# Sheet_1.net
KiCad netlist of a schematic drawn in Altium Designer
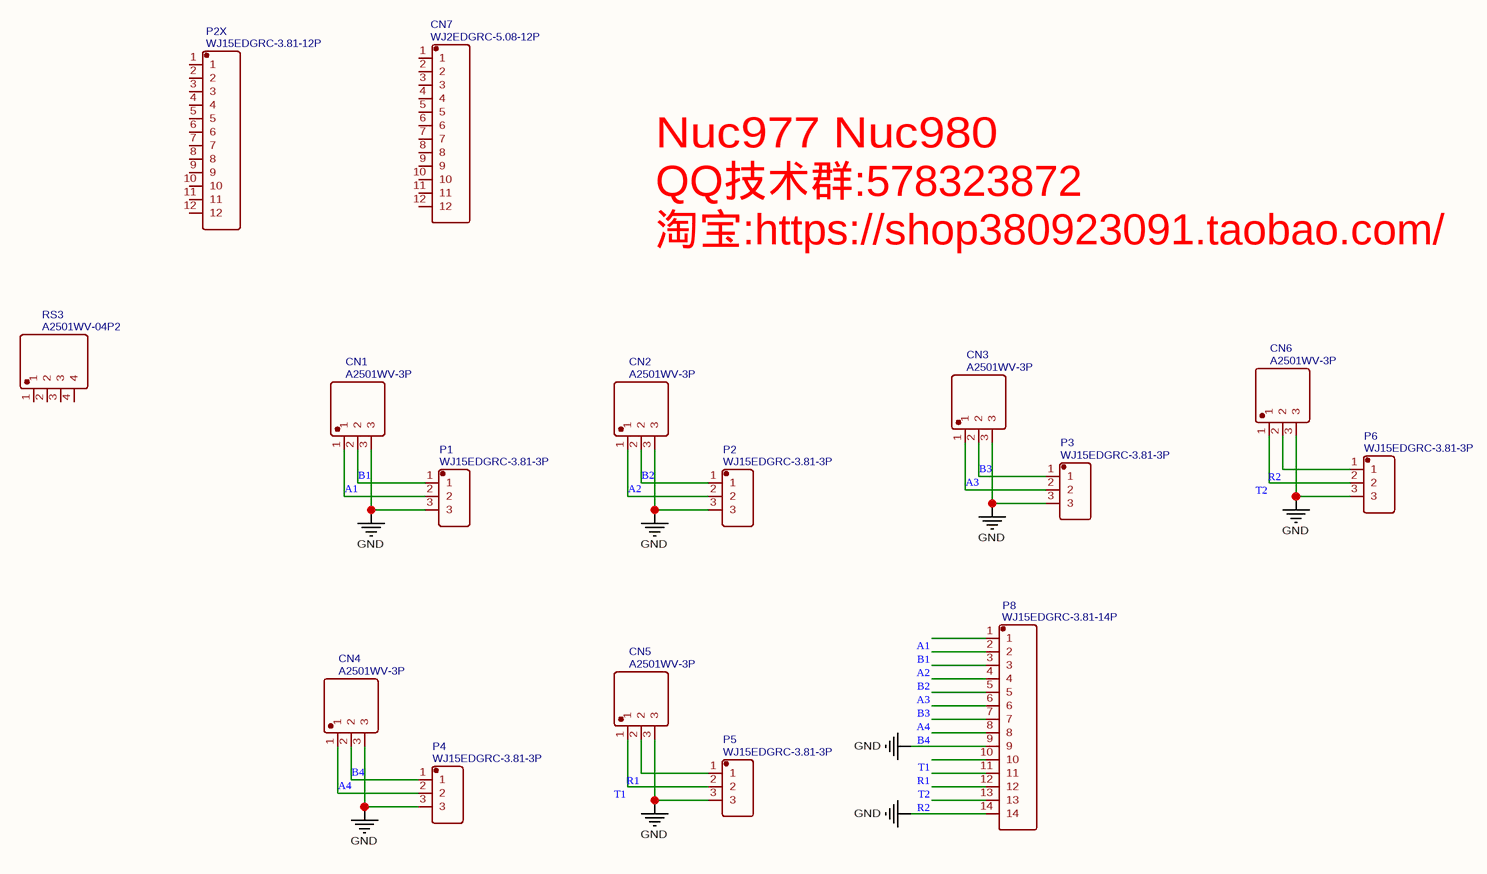
[diagram p0: Sheet_1.schdoc]

(export (version "E")
  (design (tool "Eeschema 10.0.6"))
  (components
    (comp (ref "CN1")
      (value "A2501WV-3P")
      (fields (field (name "BOM_SUPPLIER PART") "C225389") (field (name "CONTRIBUTOR") "LCSC"))
      (libsource (lib "altium-import") (part "root_1_A2501WV-3P_"))
    )
    (comp (ref "CN2")
      (value "A2501WV-3P")
      (fields (field (name "BOM_SUPPLIER PART") "C225389") (field (name "CONTRIBUTOR") "LCSC"))
      (libsource (lib "altium-import") (part "root_1_A2501WV-3P_"))
    )
    (comp (ref "CN3")
      (value "A2501WV-3P")
      (fields (field (name "BOM_SUPPLIER PART") "C225389") (field (name "CONTRIBUTOR") "LCSC"))
      (libsource (lib "altium-import") (part "root_1_A2501WV-3P_"))
    )
    (comp (ref "CN4")
      (value "A2501WV-3P")
      (fields (field (name "BOM_SUPPLIER PART") "C225389") (field (name "CONTRIBUTOR") "LCSC"))
      (libsource (lib "altium-import") (part "root_1_A2501WV-3P_"))
    )
    (comp (ref "CN5")
      (value "A2501WV-3P")
      (fields (field (name "BOM_SUPPLIER PART") "C225389") (field (name "CONTRIBUTOR") "LCSC"))
      (libsource (lib "altium-import") (part "root_1_A2501WV-3P_"))
    )
    (comp (ref "CN6")
      (value "A2501WV-3P")
      (fields (field (name "BOM_SUPPLIER PART") "C225389") (field (name "CONTRIBUTOR") "LCSC"))
      (libsource (lib "altium-import") (part "root_1_A2501WV-3P_"))
    )
    (comp (ref "CN7")
      (value "WJ2EDGRC-5.08-12P")
      (fields (field (name "BOM_SUPPLIER PART") "C127848") (field (name "CONTRIBUTOR") "LCSC"))
      (libsource (lib "altium-import") (part "root_0_WJ2EDGRC-5.08-12P_"))
    )
    (comp (ref "P1")
      (value "WJ15EDGRC-3.81-3P")
      (fields (field (name "BOM_SUPPLIER PART") "C8406"))
      (libsource (lib "altium-import") (part "root_0_WJ15EDGRC-3.81-3P_"))
    )
    (comp (ref "P2")
      (value "WJ15EDGRC-3.81-3P")
      (fields (field (name "BOM_SUPPLIER PART") "C8406"))
      (libsource (lib "altium-import") (part "root_0_WJ15EDGRC-3.81-3P_"))
    )
    (comp (ref "P2X")
      (value "WJ15EDGRC-3.81-12P")
      (fields (field (name "BOM_SUPPLIER PART") "C35591"))
      (libsource (lib "altium-import") (part "root_0_WJ15EDGRC-3.81-12P_"))
    )
    (comp (ref "P3")
      (value "WJ15EDGRC-3.81-3P")
      (fields (field (name "BOM_SUPPLIER PART") "C8406"))
      (libsource (lib "altium-import") (part "root_0_WJ15EDGRC-3.81-3P_"))
    )
    (comp (ref "P4")
      (value "WJ15EDGRC-3.81-3P")
      (fields (field (name "BOM_SUPPLIER PART") "C8406"))
      (libsource (lib "altium-import") (part "root_0_WJ15EDGRC-3.81-3P_"))
    )
    (comp (ref "P5")
      (value "WJ15EDGRC-3.81-3P")
      (fields (field (name "BOM_SUPPLIER PART") "C8406"))
      (libsource (lib "altium-import") (part "root_0_WJ15EDGRC-3.81-3P_"))
    )
    (comp (ref "P6")
      (value "WJ15EDGRC-3.81-3P")
      (fields (field (name "BOM_SUPPLIER PART") "C8406"))
      (libsource (lib "altium-import") (part "root_0_WJ15EDGRC-3.81-3P_"))
    )
    (comp (ref "P8")
      (value "WJ15EDGRC-3.81-14P")
      (fields (field (name "BOM_SUPPLIER PART") "C31933"))
      (libsource (lib "altium-import") (part "root_0_WJ15EDGRC-3.81-14P_"))
    )
    (comp (ref "RS3")
      (value "A2501WV-04P2")
      (fields (field (name "BOM_SUPPLIER PART") "C352914") (field (name "CONTRIBUTOR") "LCSC"))
      (libsource (lib "altium-import") (part "root_1_A2501WV-04P2_"))
    )
  )
  (nets
    (net (code "1") (name "/A1") (class "Default")
      (node (ref "CN1") (pin "1") (pinfunction "1_1") (pintype "passive"))
      (node (ref "P1") (pin "2") (pinfunction "2_2") (pintype "passive"))
      (node (ref "P8") (pin "1") (pinfunction "1_1") (pintype "passive"))
    )
    (net (code "2") (name "/A2") (class "Default")
      (node (ref "CN2") (pin "1") (pinfunction "1_1") (pintype "passive"))
      (node (ref "P2") (pin "2") (pinfunction "2_2") (pintype "passive"))
      (node (ref "P8") (pin "3") (pinfunction "3_3") (pintype "passive"))
    )
    (net (code "3") (name "/A3") (class "Default")
      (node (ref "CN3") (pin "1") (pinfunction "1_1") (pintype "passive"))
      (node (ref "P3") (pin "2") (pinfunction "2_2") (pintype "passive"))
      (node (ref "P8") (pin "5") (pinfunction "5_5") (pintype "passive"))
    )
    (net (code "4") (name "/A4") (class "Default")
      (node (ref "CN4") (pin "1") (pinfunction "1_1") (pintype "passive"))
      (node (ref "P4") (pin "2") (pinfunction "2_2") (pintype "passive"))
      (node (ref "P8") (pin "7") (pinfunction "7_7") (pintype "passive"))
    )
    (net (code "5") (name "/B1") (class "Default")
      (node (ref "CN1") (pin "2") (pinfunction "2_2") (pintype "passive"))
      (node (ref "P1") (pin "1") (pinfunction "1_1") (pintype "passive"))
      (node (ref "P8") (pin "2") (pinfunction "2_2") (pintype "passive"))
    )
    (net (code "6") (name "/B2") (class "Default")
      (node (ref "CN2") (pin "2") (pinfunction "2_2") (pintype "passive"))
      (node (ref "P2") (pin "1") (pinfunction "1_1") (pintype "passive"))
      (node (ref "P8") (pin "4") (pinfunction "4_4") (pintype "passive"))
    )
    (net (code "7") (name "/B3") (class "Default")
      (node (ref "CN3") (pin "2") (pinfunction "2_2") (pintype "passive"))
      (node (ref "P3") (pin "1") (pinfunction "1_1") (pintype "passive"))
      (node (ref "P8") (pin "6") (pinfunction "6_6") (pintype "passive"))
    )
    (net (code "8") (name "/B4") (class "Default")
      (node (ref "CN4") (pin "2") (pinfunction "2_2") (pintype "passive"))
      (node (ref "P4") (pin "1") (pinfunction "1_1") (pintype "passive"))
      (node (ref "P8") (pin "8") (pinfunction "8_8") (pintype "passive"))
    )
    (net (code "9") (name "/R1") (class "Default")
      (node (ref "CN5") (pin "2") (pinfunction "2_2") (pintype "passive"))
      (node (ref "P5") (pin "1") (pinfunction "1_1") (pintype "passive"))
      (node (ref "P8") (pin "11") (pinfunction "11_11") (pintype "passive"))
    )
    (net (code "10") (name "/R2") (class "Default")
      (node (ref "CN6") (pin "2") (pinfunction "2_2") (pintype "passive"))
      (node (ref "P6") (pin "1") (pinfunction "1_1") (pintype "passive"))
      (node (ref "P8") (pin "13") (pinfunction "13_13") (pintype "passive"))
    )
    (net (code "11") (name "/T1") (class "Default")
      (node (ref "CN5") (pin "1") (pinfunction "1_1") (pintype "passive"))
      (node (ref "P5") (pin "2") (pinfunction "2_2") (pintype "passive"))
      (node (ref "P8") (pin "10") (pinfunction "10_10") (pintype "passive"))
    )
    (net (code "12") (name "/T2") (class "Default")
      (node (ref "CN6") (pin "1") (pinfunction "1_1") (pintype "passive"))
      (node (ref "P6") (pin "2") (pinfunction "2_2") (pintype "passive"))
      (node (ref "P8") (pin "12") (pinfunction "12_12") (pintype "passive"))
    )
    (net (code "13") (name "GND") (class "Default")
      (node (ref "CN1") (pin "3") (pinfunction "3_3") (pintype "passive"))
      (node (ref "CN2") (pin "3") (pinfunction "3_3") (pintype "passive"))
      (node (ref "CN3") (pin "3") (pinfunction "3_3") (pintype "passive"))
      (node (ref "CN4") (pin "3") (pinfunction "3_3") (pintype "passive"))
      (node (ref "CN5") (pin "3") (pinfunction "3_3") (pintype "passive"))
      (node (ref "CN6") (pin "3") (pinfunction "3_3") (pintype "passive"))
      (node (ref "P1") (pin "3") (pinfunction "3_3") (pintype "passive"))
      (node (ref "P2") (pin "3") (pinfunction "3_3") (pintype "passive"))
      (node (ref "P3") (pin "3") (pinfunction "3_3") (pintype "passive"))
      (node (ref "P4") (pin "3") (pinfunction "3_3") (pintype "passive"))
      (node (ref "P5") (pin "3") (pinfunction "3_3") (pintype "passive"))
      (node (ref "P6") (pin "3") (pinfunction "3_3") (pintype "passive"))
      (node (ref "P8") (pin "14") (pinfunction "14_14") (pintype "passive"))
      (node (ref "P8") (pin "9") (pinfunction "9_9") (pintype "passive"))
    )
    (net (code "14") (name "unconnected-(CN7-Pad1)") (class "Default")
      (node (ref "CN7") (pin "1") (pinfunction "1_1") (pintype "passive"))
    )
    (net (code "15") (name "unconnected-(CN7-Pad2)") (class "Default")
      (node (ref "CN7") (pin "2") (pinfunction "2_2") (pintype "passive"))
    )
    (net (code "16") (name "unconnected-(CN7-Pad3)") (class "Default")
      (node (ref "CN7") (pin "3") (pinfunction "3_3") (pintype "passive"))
    )
    (net (code "17") (name "unconnected-(CN7-Pad4)") (class "Default")
      (node (ref "CN7") (pin "4") (pinfunction "4_4") (pintype "passive"))
    )
    (net (code "18") (name "unconnected-(CN7-Pad5)") (class "Default")
      (node (ref "CN7") (pin "5") (pinfunction "5_5") (pintype "passive"))
    )
    (net (code "19") (name "unconnected-(CN7-Pad6)") (class "Default")
      (node (ref "CN7") (pin "6") (pinfunction "6_6") (pintype "passive"))
    )
    (net (code "20") (name "unconnected-(CN7-Pad7)") (class "Default")
      (node (ref "CN7") (pin "7") (pinfunction "7_7") (pintype "passive"))
    )
    (net (code "21") (name "unconnected-(CN7-Pad8)") (class "Default")
      (node (ref "CN7") (pin "8") (pinfunction "8_8") (pintype "passive"))
    )
    (net (code "22") (name "unconnected-(CN7-Pad9)") (class "Default")
      (node (ref "CN7") (pin "9") (pinfunction "9_9") (pintype "passive"))
    )
    (net (code "23") (name "unconnected-(CN7-Pad10)") (class "Default")
      (node (ref "CN7") (pin "10") (pinfunction "10_10") (pintype "passive"))
    )
    (net (code "24") (name "unconnected-(CN7-Pad11)") (class "Default")
      (node (ref "CN7") (pin "11") (pinfunction "11_11") (pintype "passive"))
    )
    (net (code "25") (name "unconnected-(CN7-Pad12)") (class "Default")
      (node (ref "CN7") (pin "12") (pinfunction "12_12") (pintype "passive"))
    )
    (net (code "26") (name "unconnected-(P2X-Pad1)") (class "Default")
      (node (ref "P2X") (pin "1") (pinfunction "1_1") (pintype "passive"))
    )
    (net (code "27") (name "unconnected-(P2X-Pad2)") (class "Default")
      (node (ref "P2X") (pin "2") (pinfunction "2_2") (pintype "passive"))
    )
    (net (code "28") (name "unconnected-(P2X-Pad3)") (class "Default")
      (node (ref "P2X") (pin "3") (pinfunction "3_3") (pintype "passive"))
    )
    (net (code "29") (name "unconnected-(P2X-Pad4)") (class "Default")
      (node (ref "P2X") (pin "4") (pinfunction "4_4") (pintype "passive"))
    )
    (net (code "30") (name "unconnected-(P2X-Pad5)") (class "Default")
      (node (ref "P2X") (pin "5") (pinfunction "5_5") (pintype "passive"))
    )
    (net (code "31") (name "unconnected-(P2X-Pad6)") (class "Default")
      (node (ref "P2X") (pin "6") (pinfunction "6_6") (pintype "passive"))
    )
    (net (code "32") (name "unconnected-(P2X-Pad7)") (class "Default")
      (node (ref "P2X") (pin "7") (pinfunction "7_7") (pintype "passive"))
    )
    (net (code "33") (name "unconnected-(P2X-Pad8)") (class "Default")
      (node (ref "P2X") (pin "8") (pinfunction "8_8") (pintype "passive"))
    )
    (net (code "34") (name "unconnected-(P2X-Pad9)") (class "Default")
      (node (ref "P2X") (pin "9") (pinfunction "9_9") (pintype "passive"))
    )
    (net (code "35") (name "unconnected-(P2X-Pad10)") (class "Default")
      (node (ref "P2X") (pin "10") (pinfunction "10_10") (pintype "passive"))
    )
    (net (code "36") (name "unconnected-(P2X-Pad11)") (class "Default")
      (node (ref "P2X") (pin "11") (pinfunction "11_11") (pintype "passive"))
    )
    (net (code "37") (name "unconnected-(P2X-Pad12)") (class "Default")
      (node (ref "P2X") (pin "12") (pinfunction "12_12") (pintype "passive"))
    )
    (net (code "38") (name "unconnected-(RS3-Pad1)") (class "Default")
      (node (ref "RS3") (pin "1") (pinfunction "1_1") (pintype "passive"))
    )
    (net (code "39") (name "unconnected-(RS3-Pad2)") (class "Default")
      (node (ref "RS3") (pin "2") (pinfunction "2_2") (pintype "passive"))
    )
    (net (code "40") (name "unconnected-(RS3-Pad3)") (class "Default")
      (node (ref "RS3") (pin "3") (pinfunction "3_3") (pintype "passive"))
    )
    (net (code "41") (name "unconnected-(RS3-Pad4)") (class "Default")
      (node (ref "RS3") (pin "4") (pinfunction "4_4") (pintype "passive"))
    )
  )
)
